# TopLevel.net
KiCad netlist of a schematic drawn in Altium Designer
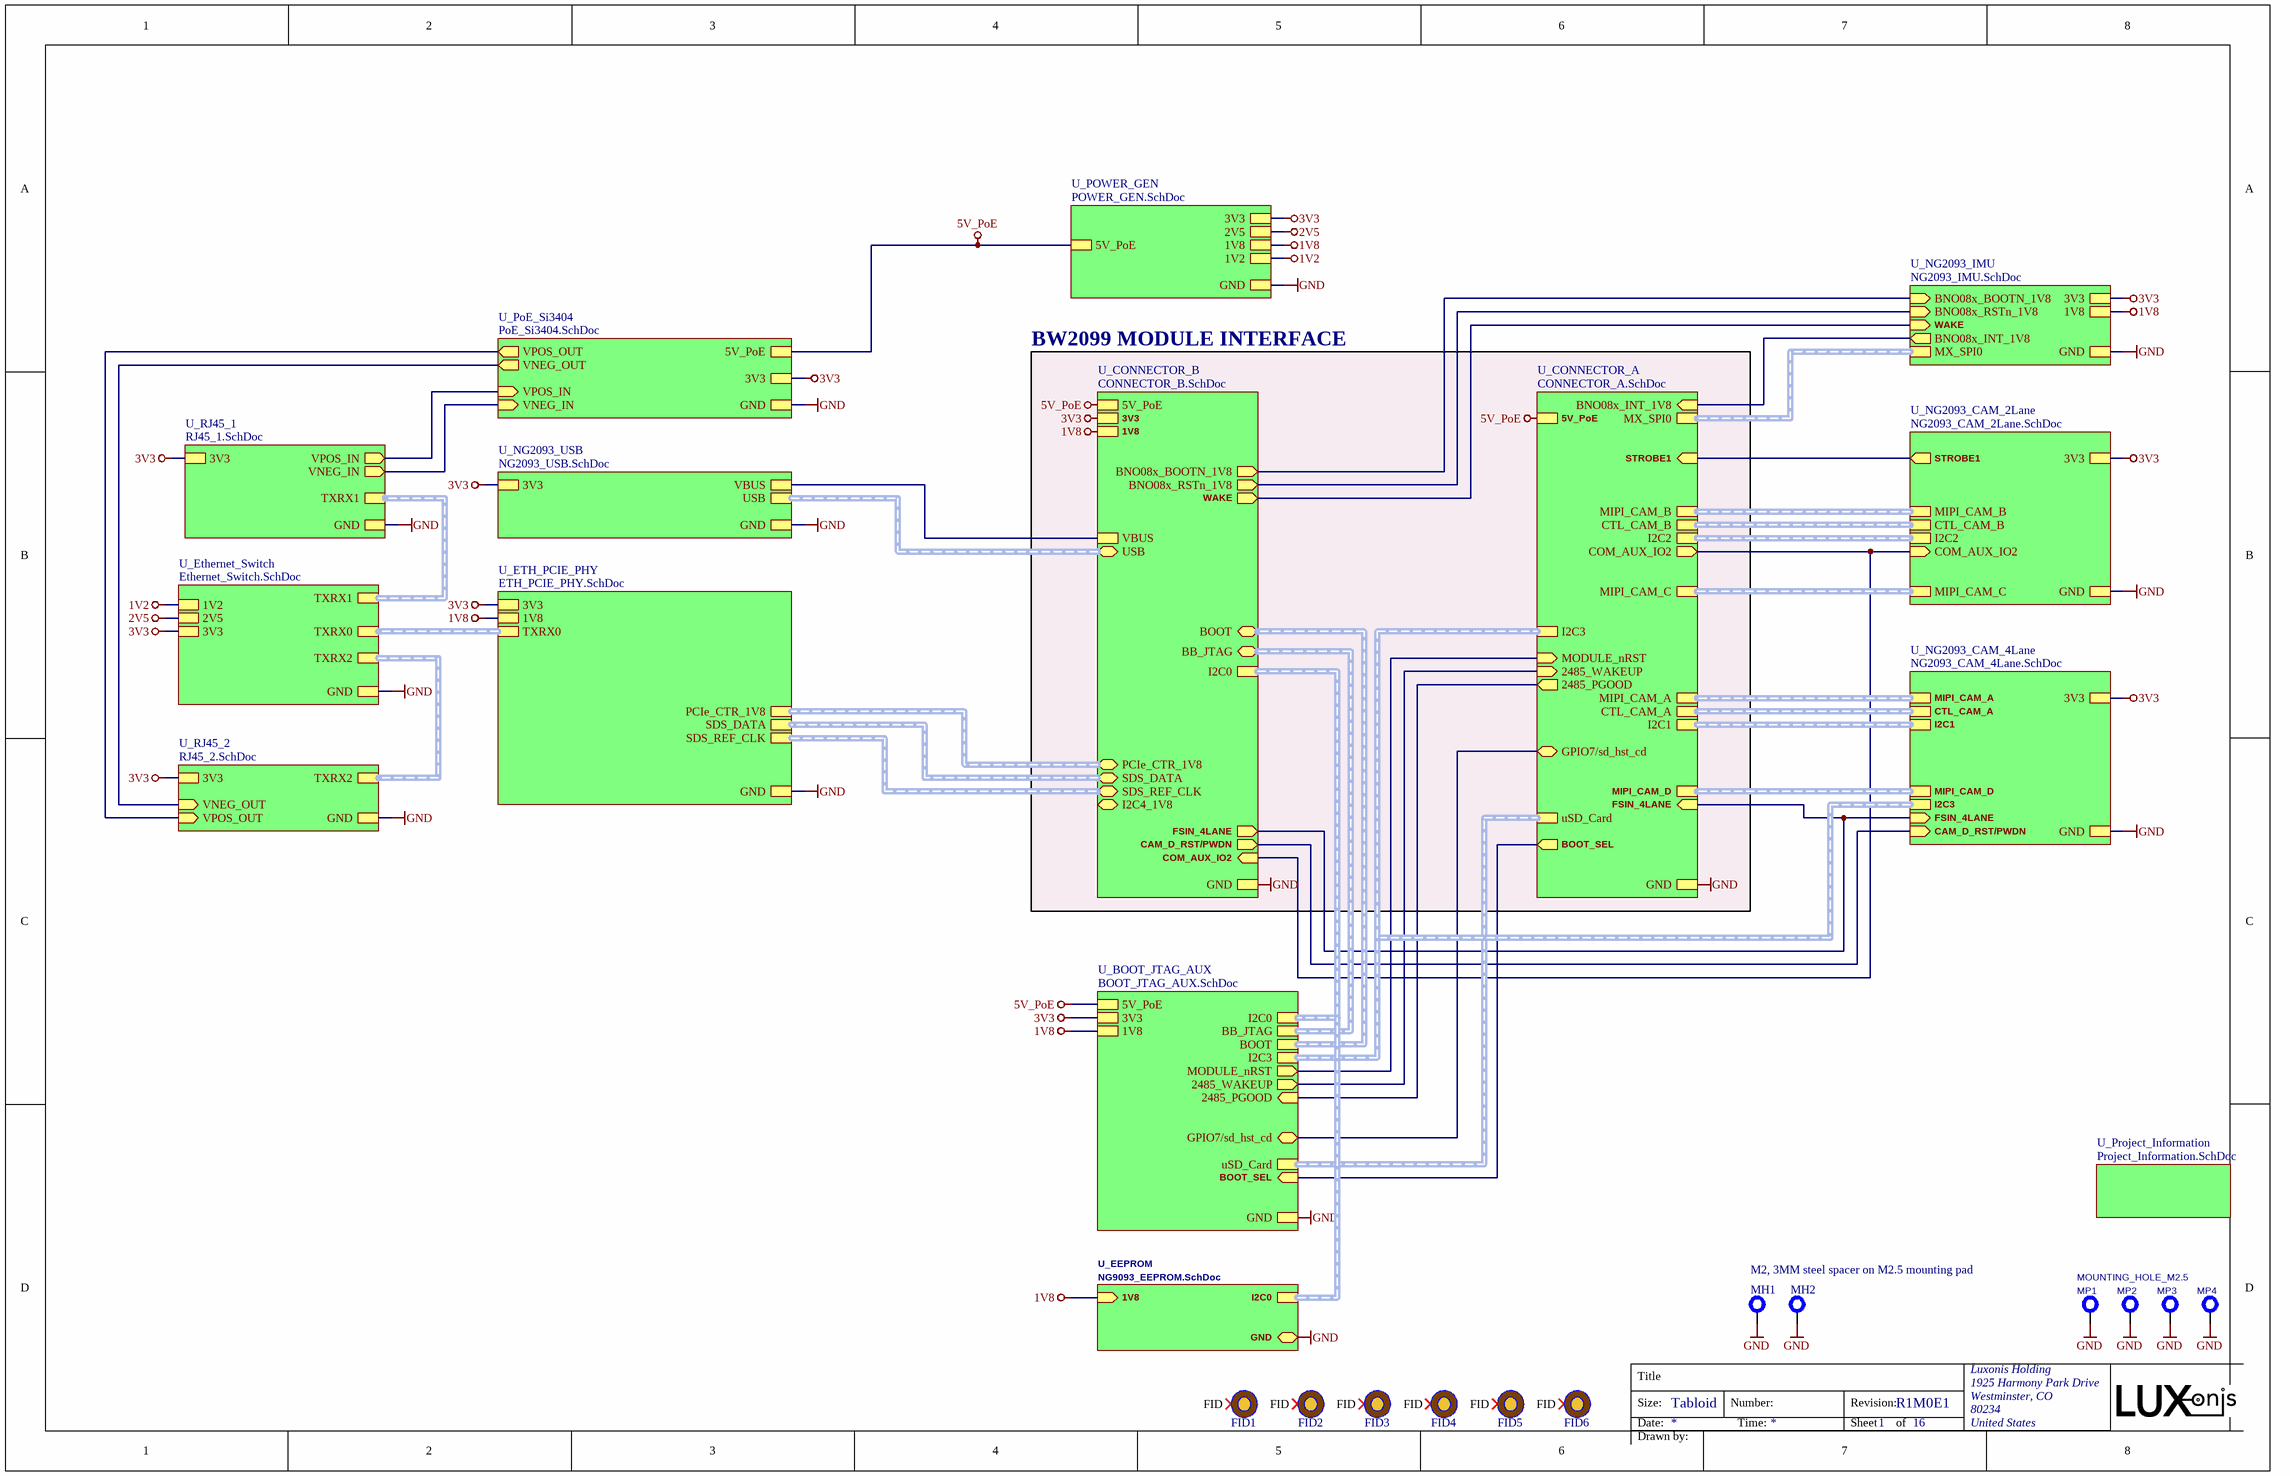
[diagram p0: TopLevel.SchDoc]

(export (version "E")
  (design (tool "Eeschema 10.0.6"))
  (components
    (comp (ref "FID1")
      (value "FIDUCIAL_ROUND_1MM")
      (footprint "LuxonisMaster:FIDUCIAL_ROUND_1MM")
      (description "Fiducial with various available footprints")
      (libsource (lib "LuxonisMaster") (part "FIDUCIAL"))
    )
    (comp (ref "FID2")
      (value "FIDUCIAL_ROUND_1MM")
      (footprint "LuxonisMaster:FIDUCIAL_ROUND_1MM")
      (description "Fiducial with various available footprints")
      (libsource (lib "LuxonisMaster") (part "FIDUCIAL"))
    )
    (comp (ref "FID3")
      (value "FIDUCIAL_ROUND_1MM")
      (footprint "LuxonisMaster:FIDUCIAL_ROUND_1MM")
      (description "Fiducial with various available footprints")
      (libsource (lib "LuxonisMaster") (part "FIDUCIAL"))
    )
    (comp (ref "FID4")
      (value "FIDUCIAL_ROUND_1MM")
      (footprint "LuxonisMaster:FIDUCIAL_ROUND_1MM")
      (description "Fiducial with various available footprints")
      (libsource (lib "LuxonisMaster") (part "FIDUCIAL"))
    )
    (comp (ref "FID5")
      (value "FIDUCIAL_ROUND_1MM")
      (footprint "LuxonisMaster:FIDUCIAL_ROUND_1MM")
      (description "Fiducial with various available footprints")
      (libsource (lib "LuxonisMaster") (part "FIDUCIAL"))
    )
    (comp (ref "FID6")
      (value "FIDUCIAL_ROUND_1MM")
      (footprint "LuxonisMaster:FIDUCIAL_ROUND_1MM")
      (description "Fiducial with various available footprints")
      (libsource (lib "LuxonisMaster") (part "FIDUCIAL"))
    )
    (comp (ref "MH1")
      (value "M2, 3MM steel spacer on M2.5 mounting pad")
      (footprint "LuxonisMaster:9774030243R")
      (description "MP ROUND STANDOFF M2X0.4 STEEL 3MM")
      (libsource (lib "LuxonisMaster") (part "9774030243R"))
    )
    (comp (ref "MH2")
      (value "M2, 3MM steel spacer on M2.5 mounting pad")
      (footprint "LuxonisMaster:9774030243R")
      (description "MP ROUND STANDOFF M2X0.4 STEEL 3MM")
      (libsource (lib "LuxonisMaster") (part "9774030243R"))
    )
    (comp (ref "MP1")
      (value "MOUNTING_HOLE_M2.5")
      (footprint "LuxonisMaster:MOUNTING_HOLE_M2.5")
      (description "=CurrentFootprint")
      (libsource (lib "LuxonisMaster") (part "MP_Mounting-Holes"))
    )
    (comp (ref "MP2")
      (value "MOUNTING_HOLE_M2.5")
      (footprint "LuxonisMaster:MOUNTING_HOLE_M2.5")
      (description "=CurrentFootprint")
      (libsource (lib "LuxonisMaster") (part "MP_Mounting-Holes"))
    )
    (comp (ref "MP3")
      (value "MOUNTING_HOLE_M2.5")
      (footprint "LuxonisMaster:MOUNTING_HOLE_M2.5")
      (description "=CurrentFootprint")
      (libsource (lib "LuxonisMaster") (part "MP_Mounting-Holes"))
    )
    (comp (ref "MP4")
      (value "MOUNTING_HOLE_M2.5")
      (footprint "LuxonisMaster:MOUNTING_HOLE_M2.5")
      (description "=CurrentFootprint")
      (libsource (lib "LuxonisMaster") (part "MP_Mounting-Holes"))
    )
  )
  (nets
    (net (code "46") (name "GND") (class "Default")
      (node (ref "MH1") (pin "1") (pintype "passive"))
      (node (ref "MH2") (pin "1") (pintype "passive"))
      (node (ref "MP1") (pin "1") (pintype "passive"))
      (node (ref "MP2") (pin "1") (pintype "passive"))
      (node (ref "MP3") (pin "1") (pintype "passive"))
      (node (ref "MP4") (pin "1") (pintype "passive"))
    )
    (net (code "47") (name "unconnected-(FID1-PadFID)") (class "Default")
      (node (ref "FID1") (pin "FID") (pinfunction "FID_FID") (pintype "input+no_connect"))
    )
    (net (code "48") (name "unconnected-(FID2-PadFID)") (class "Default")
      (node (ref "FID2") (pin "FID") (pinfunction "FID_FID") (pintype "input+no_connect"))
    )
    (net (code "49") (name "unconnected-(FID3-PadFID)") (class "Default")
      (node (ref "FID3") (pin "FID") (pinfunction "FID_FID") (pintype "input+no_connect"))
    )
    (net (code "50") (name "unconnected-(FID4-PadFID)") (class "Default")
      (node (ref "FID4") (pin "FID") (pinfunction "FID_FID") (pintype "input+no_connect"))
    )
    (net (code "51") (name "unconnected-(FID5-PadFID)") (class "Default")
      (node (ref "FID5") (pin "FID") (pinfunction "FID_FID") (pintype "input+no_connect"))
    )
    (net (code "52") (name "unconnected-(FID6-PadFID)") (class "Default")
      (node (ref "FID6") (pin "FID") (pinfunction "FID_FID") (pintype "input+no_connect"))
    )
  )
)
